# Power_Supply.net
KiCad netlist of a schematic drawn in Altium Designer
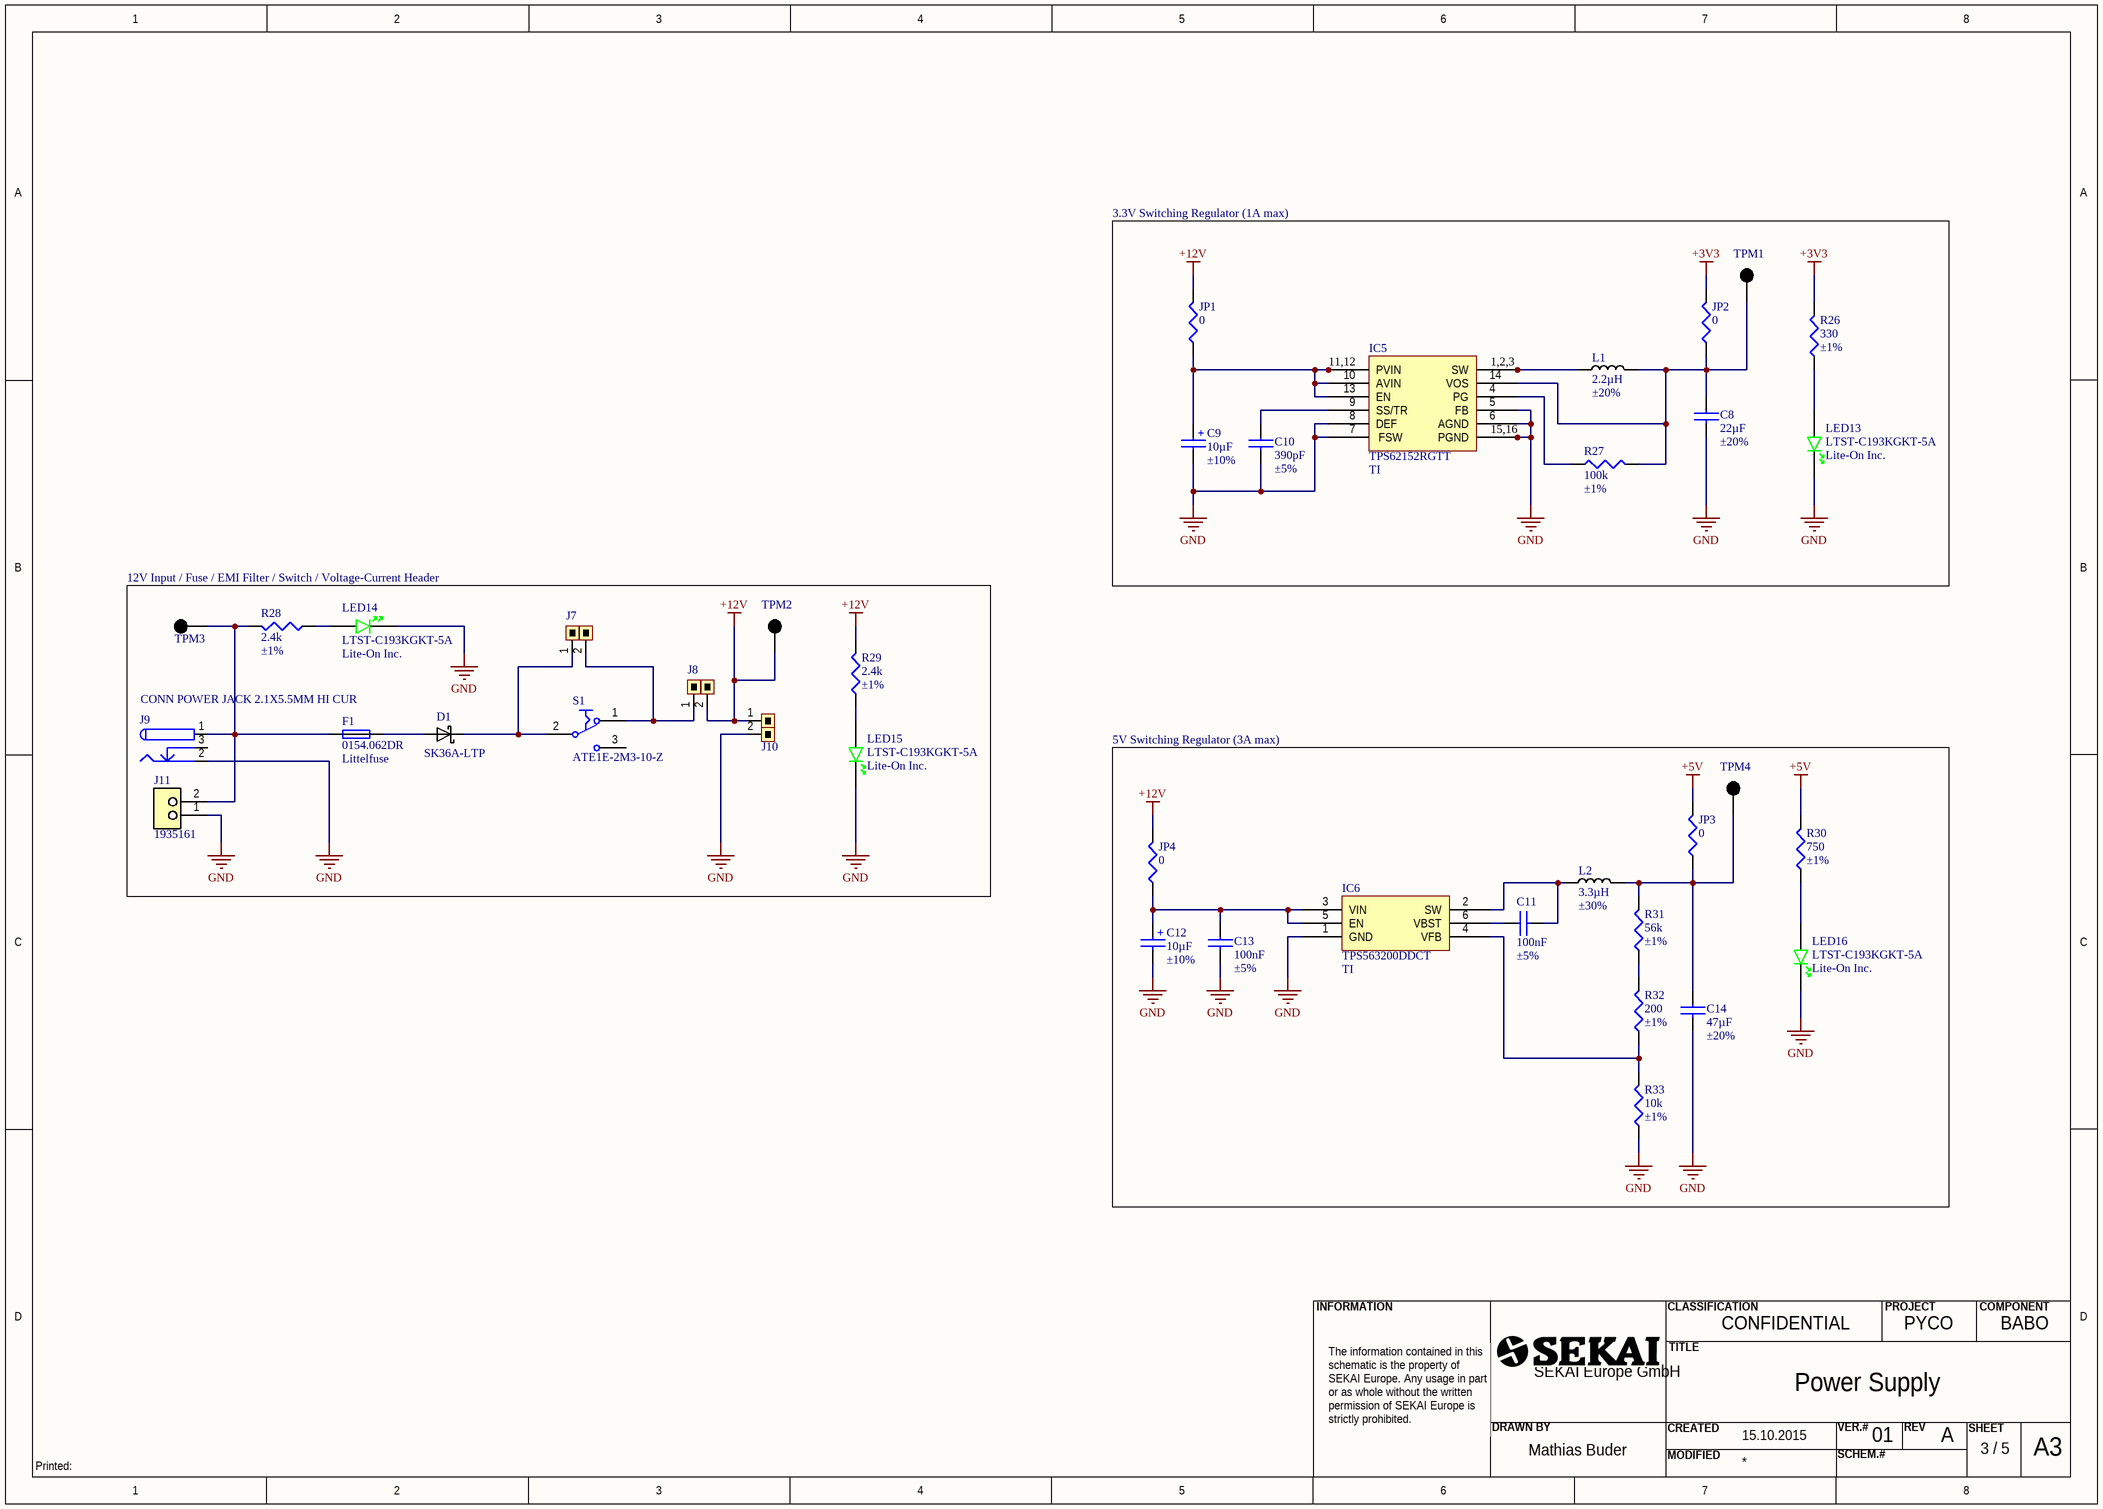
[diagram p0: Power Supply.SchDoc]

(export (version "E")
  (design (tool "Eeschema 10.0.6"))
  (components
    (comp (ref "C8")
      (value "C2012X5R0J226M125AC")
      (footprint "C0805")
      (description "CAP CER 22UF 6.3V X5R 0805")
      (fields
        (field (name "MANUFACTURER") "TDK Corporation")
        (field (name "CAPACITANCE") "22µF")
        (field (name "TOLERANCE") "±20%")
      )
      (libsource (lib "CAP") (part "C2012X5R0J226M125AC"))
    )
    (comp (ref "C9")
      (value "T491A106K016AT")
      (footprint "C1206")
      (description "CAP TANT 10UF 16V 10% 1206")
      (fields
        (field (name "MANUFACTURER") "Kemet")
        (field (name "KAPAZITÄT") "10µF")
        (field (name "TOLERANZ") "±10%")
      )
      (libsource (lib "CAP") (part "T491A106K016AT"))
    )
    (comp (ref "C10")
      (value "GRM1885C1H391JA01D")
      (footprint "C0603")
      (description "CAP CER 390PF 50V NP0 0603")
      (fields
        (field (name "MANUFACTURER") "Murata Electronics North America")
        (field (name "CAPACITANCE") "390pF")
        (field (name "TOLERANCE") "±5%")
      )
      (libsource (lib "CAP") (part "GRM1885C1H391JA01D"))
    )
    (comp (ref "C11")
      (value "C0603C104J4RACTU")
      (footprint "C0603")
      (description "CAP CER 100NF 16V 5% X7R 0603")
      (fields
        (field (name "MANUFACTURER") "Kemet")
        (field (name "KAPAZITÄT") "100nF")
        (field (name "TOLERANZ") "±5%")
      )
      (libsource (lib "CAP") (part "C0603C104J4RACTU"))
    )
    (comp (ref "C12")
      (value "T491A106K016AT")
      (footprint "C1206")
      (description "CAP TANT 10UF 16V 10% 1206")
      (fields
        (field (name "MANUFACTURER") "Kemet")
        (field (name "KAPAZITÄT") "10µF")
        (field (name "TOLERANZ") "±10%")
      )
      (libsource (lib "CAP") (part "T491A106K016AT"))
    )
    (comp (ref "C13")
      (value "C0603C104J4RACTU")
      (footprint "C0603")
      (description "CAP CER 100NF 16V 5% X7R 0603")
      (fields
        (field (name "MANUFACTURER") "Kemet")
        (field (name "KAPAZITÄT") "100nF")
        (field (name "TOLERANZ") "±5%")
      )
      (libsource (lib "CAP") (part "C0603C104J4RACTU"))
    )
    (comp (ref "C14")
      (value "C3216X6S1A476M160AC")
      (footprint "C1206")
      (description "CAP CER 47UF 10V X6S 1206")
      (fields
        (field (name "MANUFACTURER") "TDK Corporation")
        (field (name "CAPACITANCE") "47µF")
        (field (name "TOLERANCE") "±20%")
      )
      (libsource (lib "CAP") (part "C3216X6S1A476M160AC"))
    )
    (comp (ref "D1")
      (value "SK36A-LTP")
      (footprint "DO-214AC")
      (description "DIODE SCHOTTKY 60V 3A DO214AC")
      (fields (field (name "MANUFACTURER") "Micro Commercial Co"))
      (libsource (lib "DIODE_MicroCommercial") (part "SK36A-LTP"))
    )
    (comp (ref "F1")
      (value "0154.062DR")
      (footprint "0154.062DR")
      (description "FUSE BRD MNT 62MA 125VAC/VDC SMD")
      (fields (field (name "MANUFACTURER") "Littelfuse"))
      (libsource (lib "FUSE_LittleFuse") (part "0154.062DR"))
    )
    (comp (ref "IC5")
      (value "TPS62152RGTT")
      (footprint "QFN16")
      (description "IC REG BUCK 3.3V 1A SYNC 16QFN")
      (fields (field (name "MANUFACTURER") "TI"))
      (libsource (lib "BUCK_TI") (part "TPS62152RGTT"))
    )
    (comp (ref "IC6")
      (value "TPS563200DDCT")
      (footprint "SOT23-6")
      (description "IC REG BUCK ADJ 3A SYNC 6SOT")
      (fields (field (name "MANUFACTURER") "TI"))
      (libsource (lib "BUCK_TI") (part "TPS563200DDCT"))
    )
    (comp (ref "J7")
      (value "1x2")
      (footprint "Post Height Terminal Strip 1x2")
      (libsource (lib "") (part "Header 1x2_1"))
    )
    (comp (ref "J8")
      (value "1x2")
      (footprint "Post Height Terminal Strip 1x2")
      (libsource (lib "") (part "Header 1x2_1"))
    )
    (comp (ref "J9")
      (value "CONN POWER JACK 2.1X5.5MM HI CUR")
      (footprint "CP-002AHPJCT-ND")
      (fields
        (field (name "MANUFACTURER") "CUI Inc")
        (field (name "MANUFACTURER PART NUMBER") "PJ-002AH-SMT-TR")
      )
      (libsource (lib "CON_DC") (part "PJ-002AH-SMT-TR"))
    )
    (comp (ref "J10")
      (value "1x2")
      (footprint "Post Height Terminal Strip 1x2")
      (libsource (lib "CON_Standard") (part "Header 1x2"))
    )
    (comp (ref "J11")
      (value "1935161")
      (footprint "2 POS Screw Terminal")
      (description "TERM BLOCK PCB 2POS 5.0MM GREEN")
      (fields (field (name "MANUFACTURER") "Phoenix Contact") (field (name "VOLTAGE") "300V"))
      (libsource (lib "CON_PHOENIX") (part "1935161"))
    )
    (comp (ref "JP1")
      (value "ERJ-3GEY0R00V")
      (footprint "R0603")
      (description "RES SMD 0 OHM JUMPER 1/10W")
      (fields
        (field (name "MANUFACTURER") "Panasonic Electronic Components")
        (field (name "RESISTANCE (OHMS)") "0")
      )
      (libsource (lib "RES") (part "ERJ-3GEY0R00V"))
    )
    (comp (ref "JP2")
      (value "ERJ-3GEY0R00V")
      (footprint "R0603")
      (description "RES SMD 0 OHM JUMPER 1/10W")
      (fields
        (field (name "MANUFACTURER") "Panasonic Electronic Components")
        (field (name "RESISTANCE (OHMS)") "0")
      )
      (libsource (lib "RES") (part "ERJ-3GEY0R00V"))
    )
    (comp (ref "JP3")
      (value "ERJ-3GEY0R00V")
      (footprint "R0603")
      (description "RES SMD 0 OHM JUMPER 1/10W")
      (fields
        (field (name "MANUFACTURER") "Panasonic Electronic Components")
        (field (name "RESISTANCE (OHMS)") "0")
      )
      (libsource (lib "RES") (part "ERJ-3GEY0R00V"))
    )
    (comp (ref "JP4")
      (value "ERJ-3GEY0R00V")
      (footprint "R0603")
      (description "RES SMD 0 OHM JUMPER 1/10W")
      (fields
        (field (name "MANUFACTURER") "Panasonic Electronic Components")
        (field (name "RESISTANCE (OHMS)") "0")
      )
      (libsource (lib "RES") (part "ERJ-3GEY0R00V"))
    )
    (comp (ref "L1")
      (value "SDR0403-2R2ML")
      (footprint "IND-LQH32CN220K53L 2 11")
      (description "FIXED IND 2.2UH 2.6A 47 MOHM SMD")
      (fields
        (field (name "MANUFACTURER") "Bourns Inc.")
        (field (name "INDUCTANCE") "2.2µH")
        (field (name "TOLERANCE") "±20%")
      )
      (libsource (lib "IND") (part "SDR0403-2R2ML"))
    )
    (comp (ref "L2")
      (value "SRR6038-3R3Y")
      (footprint "SRR6038-3R3Y")
      (description "FIXED IND 3.3UH 3.5A 20 MOHM SMD")
      (fields
        (field (name "MANUFACTURER") "Bourns")
        (field (name "INDUCTANCE") "3.3µH")
        (field (name "TOLERANCE") "±30%")
      )
      (libsource (lib "IND") (part "SRR6038-3R3Y"))
    )
    (comp (ref "LED13")
      (value "LTST-C193KGKT-5A")
      (footprint "LED0603-GREEN")
      (description "LED GREEN CLEAR 0603 SMD")
      (fields (field (name "MANUFACTURER") "Lite-On Inc."))
      (libsource (lib "LED_Standard") (part "LTST-C193KGKT-5A"))
    )
    (comp (ref "LED14")
      (value "LTST-C193KGKT-5A")
      (footprint "LED0603-GREEN")
      (description "LED GREEN CLEAR 0603 SMD")
      (fields (field (name "MANUFACTURER") "Lite-On Inc."))
      (libsource (lib "LED_Standard") (part "LTST-C193KGKT-5A"))
    )
    (comp (ref "LED15")
      (value "LTST-C193KGKT-5A")
      (footprint "LED0603-GREEN")
      (description "LED GREEN CLEAR 0603 SMD")
      (fields (field (name "MANUFACTURER") "Lite-On Inc."))
      (libsource (lib "LED_Standard") (part "LTST-C193KGKT-5A"))
    )
    (comp (ref "LED16")
      (value "LTST-C193KGKT-5A")
      (footprint "LED0603-GREEN")
      (description "LED GREEN CLEAR 0603 SMD")
      (fields (field (name "MANUFACTURER") "Lite-On Inc."))
      (libsource (lib "LED_Standard") (part "LTST-C193KGKT-5A"))
    )
    (comp (ref "R26")
      (value "ERJ-3EKF3300V")
      (footprint "R0603")
      (description "RES SMD 330 OHM 1% 1/10W 0603")
      (fields
        (field (name "MANUFACTURER") "Panasonic Electronic Components")
        (field (name "RESISTANCE (OHMS)") "330")
        (field (name "TOLERANCE") "±1%")
      )
      (libsource (lib "RES") (part "ERJ-3EKF3300V"))
    )
    (comp (ref "R27")
      (value "ERJ-3EKF1003V")
      (footprint "R0603")
      (description "RES SMD 100K OHM 1% 1/10W 0603")
      (fields
        (field (name "MANUFACTURER") "Panasonic Electronic Components")
        (field (name "RESISTANCE (OHMS)") "100k")
        (field (name "TOLERANCE") "±1%")
      )
      (libsource (lib "RES") (part "ERJ-3EKF1003V"))
    )
    (comp (ref "R28")
      (value "ERJ-3EKF2401V")
      (footprint "R0603")
      (description "RES SMD 2.4K OHM 1% 1/10W 0603")
      (fields
        (field (name "MANUFACTURER") "Panasonic Electronic Components")
        (field (name "RESISTANCE (OHMS)") "2.4k")
        (field (name "TOLERANCE") "±1%")
      )
      (libsource (lib "RES") (part "ERJ-3EKF2401V"))
    )
    (comp (ref "R29")
      (value "ERJ-3EKF2401V")
      (footprint "R0603")
      (description "RES SMD 2.4K OHM 1% 1/10W 0603")
      (fields
        (field (name "MANUFACTURER") "Panasonic Electronic Components")
        (field (name "RESISTANCE (OHMS)") "2.4k")
        (field (name "TOLERANCE") "±1%")
      )
      (libsource (lib "RES") (part "ERJ-3EKF2401V"))
    )
    (comp (ref "R30")
      (value "ERJ-3EKF7500V")
      (footprint "R0603")
      (description "RES SMD 750 OHM 1% 1/10W 0603")
      (fields
        (field (name "MANUFACTURER") "Panasonic Electronic Components")
        (field (name "RESISTANCE (OHMS)") "750")
        (field (name "TOLERANCE") "±1%")
      )
      (libsource (lib "RES") (part "ERJ-3EKF7500V"))
    )
    (comp (ref "R31")
      (value "ERJ-3EKF5602V")
      (footprint "R0603")
      (description "RES SMD 56K OHM 1% 1/10W 0603")
      (fields
        (field (name "MANUFACTURER") "Panasonic Electronic Components")
        (field (name "RESISTANCE (OHMS)") "56k")
        (field (name "TOLERANCE") "±1%")
      )
      (libsource (lib "RES") (part "ERJ-3EKF5602V"))
    )
    (comp (ref "R32")
      (value "ERJ-3EKF2000V")
      (footprint "R0603")
      (description "RES SMD 200 OHM 1% 1/10W 0603")
      (fields
        (field (name "MANUFACTURER") "Panasonic Electronic Components")
        (field (name "RESISTANCE (OHMS)") "200")
        (field (name "TOLERANCE") "±1%")
      )
      (libsource (lib "RES") (part "ERJ-3EKF2000V"))
    )
    (comp (ref "R33")
      (value "ERJ-3EKF1002V")
      (footprint "R0603")
      (description "RES SMD 10K OHM 1% 1/10W 0603")
      (fields
        (field (name "MANUFACTURER") "Panasonic Electronic Components")
        (field (name "RESISTANCE (OHMS)") "10k")
        (field (name "TOLERANCE") "±1%")
      )
      (libsource (lib "RES") (part "ERJ-3EKF1002V"))
    )
    (comp (ref "S1")
      (value "ATE1E-2M3-10-Z")
      (footprint "ATE1E-2M3-10-Z")
      (description "SWITCH TOGGLE SPDT 50MA 48V")
      (fields (field (name "MANUFACTURER") "Copal Electronics Inc"))
      (libsource (lib "SW_MECH") (part "ATE1E-2M3-10-Z"))
    )
    (comp (ref "TPM1")
      (value "TestPoint-M")
      (footprint "TestPoint-M")
      (libsource (lib "Misc") (part "TestPoint-M"))
    )
    (comp (ref "TPM2")
      (value "TestPoint-M")
      (footprint "TestPoint-M")
      (libsource (lib "Misc") (part "TestPoint-M"))
    )
    (comp (ref "TPM3")
      (value "TestPoint-M")
      (footprint "TestPoint-M")
      (libsource (lib "Misc") (part "TestPoint-M"))
    )
    (comp (ref "TPM4")
      (value "TestPoint-M")
      (footprint "TestPoint-M")
      (libsource (lib "Misc") (part "TestPoint-M"))
    )
  )
  (nets
    (net (code "1") (name "+3V3") (class "Default")
      (node (ref "JP2") (pin "2") (pinfunction "2_2") (pintype "passive"))
      (node (ref "R26") (pin "2") (pinfunction "2_2") (pintype "passive"))
    )
    (net (code "2") (name "+5V") (class "Default")
      (node (ref "JP3") (pin "2") (pinfunction "2_2") (pintype "passive"))
      (node (ref "R30") (pin "2") (pinfunction "2_2") (pintype "passive"))
    )
    (net (code "3") (name "+12V") (class "Default")
      (node (ref "J10") (pin "1") (pinfunction "1_1") (pintype "passive"))
      (node (ref "J8") (pin "2") (pinfunction "2_2") (pintype "passive"))
      (node (ref "JP1") (pin "2") (pinfunction "2_2") (pintype "passive"))
      (node (ref "JP4") (pin "2") (pinfunction "2_2") (pintype "passive"))
      (node (ref "R29") (pin "2") (pinfunction "2_2") (pintype "passive"))
      (node (ref "TPM2") (pin "1") (pinfunction "1_1") (pintype "passive"))
    )
    (net (code "4") (name "GND") (class "Default")
      (node (ref "C10") (pin "2") (pinfunction "2_2") (pintype "passive"))
      (node (ref "C12") (pin "2") (pinfunction "2_2") (pintype "passive"))
      (node (ref "C13") (pin "2") (pinfunction "2_2") (pintype "passive"))
      (node (ref "C14") (pin "2") (pinfunction "2_2") (pintype "passive"))
      (node (ref "C8") (pin "2") (pinfunction "2_2") (pintype "passive"))
      (node (ref "C9") (pin "2") (pinfunction "2_2") (pintype "passive"))
      (node (ref "IC5") (pin "15") (pinfunction "PGND_15") (pintype "passive"))
      (node (ref "IC5") (pin "16") (pinfunction "PGND_16") (pintype "passive"))
      (node (ref "IC5") (pin "5") (pinfunction "FB_5") (pintype "passive"))
      (node (ref "IC5") (pin "6") (pinfunction "AGND_6") (pintype "passive"))
      (node (ref "IC5") (pin "7") (pinfunction "FSW_7") (pintype "passive"))
      (node (ref "IC5") (pin "8") (pinfunction "DEF_8") (pintype "passive"))
      (node (ref "IC6") (pin "1") (pinfunction "GND_1") (pintype "passive"))
      (node (ref "J10") (pin "2") (pinfunction "2_2") (pintype "passive"))
      (node (ref "J11") (pin "1") (pinfunction "1_1") (pintype "passive"))
      (node (ref "J9") (pin "2") (pinfunction "2_2") (pintype "power_in"))
      (node (ref "LED13") (pin "2") (pinfunction "CATHODE_2") (pintype "passive"))
      (node (ref "LED14") (pin "2") (pinfunction "CATHODE_2") (pintype "passive"))
      (node (ref "LED15") (pin "2") (pinfunction "CATHODE_2") (pintype "passive"))
      (node (ref "LED16") (pin "2") (pinfunction "CATHODE_2") (pintype "passive"))
      (node (ref "R33") (pin "1") (pinfunction "1_1") (pintype "passive"))
    )
    (net (code "5") (name "Net-(C14-Pad1)") (class "Default")
      (node (ref "C14") (pin "1") (pinfunction "1_1") (pintype "passive"))
      (node (ref "JP3") (pin "1") (pinfunction "1_1") (pintype "passive"))
      (node (ref "L2") (pin "2") (pinfunction "2_2") (pintype "passive"))
      (node (ref "R31") (pin "2") (pinfunction "2_2") (pintype "passive"))
      (node (ref "TPM4") (pin "1") (pinfunction "1_1") (pintype "passive"))
    )
    (net (code "6") (name "Net-(D1-ANODE)") (class "Default")
      (node (ref "D1") (pin "1") (pinfunction "ANODE_1") (pintype "passive"))
      (node (ref "F1") (pin "2") (pinfunction "2_2") (pintype "passive"))
    )
    (net (code "7") (name "Net-(D1-CATHODE)") (class "Default")
      (node (ref "D1") (pin "2") (pinfunction "CATHODE_2") (pintype "passive"))
      (node (ref "J7") (pin "1") (pinfunction "1_1") (pintype "passive"))
      (node (ref "S1") (pin "2") (pinfunction "2_2") (pintype "passive"))
    )
    (net (code "8") (name "Net-(F1-Pad1)") (class "Default")
      (node (ref "F1") (pin "1") (pinfunction "1_1") (pintype "passive"))
      (node (ref "J11") (pin "2") (pinfunction "2_2") (pintype "passive"))
      (node (ref "J9") (pin "1") (pinfunction "1_1") (pintype "power_in"))
      (node (ref "R28") (pin "2") (pinfunction "2_2") (pintype "passive"))
      (node (ref "TPM3") (pin "1") (pinfunction "1_1") (pintype "passive"))
    )
    (net (code "9") (name "Net-(IC5-AVIN)") (class "Default")
      (node (ref "C9") (pin "1") (pinfunction "1_1") (pintype "passive"))
      (node (ref "IC5") (pin "10") (pinfunction "AVIN_10") (pintype "passive"))
      (node (ref "IC5") (pin "11") (pinfunction "PVIN_11") (pintype "passive"))
      (node (ref "IC5") (pin "12") (pinfunction "PVIN_12") (pintype "passive"))
      (node (ref "IC5") (pin "13") (pinfunction "EN_13") (pintype "passive"))
      (node (ref "JP1") (pin "1") (pinfunction "1_1") (pintype "passive"))
    )
    (net (code "10") (name "Net-(IC5-PG)") (class "Default")
      (node (ref "IC5") (pin "4") (pinfunction "PG_4") (pintype "passive"))
      (node (ref "R27") (pin "1") (pinfunction "1_1") (pintype "passive"))
    )
    (net (code "11") (name "Net-(IC5-SS{slash}TR)") (class "Default")
      (node (ref "C10") (pin "1") (pinfunction "1_1") (pintype "passive"))
      (node (ref "IC5") (pin "9") (pinfunction "SS/TR_9") (pintype "passive"))
    )
    (net (code "12") (name "Net-(IC5-SW-Pad1)") (class "Default")
      (node (ref "IC5") (pin "1") (pinfunction "SW_1") (pintype "passive"))
      (node (ref "IC5") (pin "2") (pinfunction "SW_2") (pintype "passive"))
      (node (ref "IC5") (pin "3") (pinfunction "SW_3") (pintype "passive"))
      (node (ref "L1") (pin "1") (pinfunction "1_1") (pintype "passive"))
    )
    (net (code "13") (name "Net-(IC5-VOS)") (class "Default")
      (node (ref "C8") (pin "1") (pinfunction "1_1") (pintype "passive"))
      (node (ref "IC5") (pin "14") (pinfunction "VOS_14") (pintype "passive"))
      (node (ref "JP2") (pin "1") (pinfunction "1_1") (pintype "passive"))
      (node (ref "L1") (pin "2") (pinfunction "2_2") (pintype "passive"))
      (node (ref "R27") (pin "2") (pinfunction "2_2") (pintype "passive"))
      (node (ref "TPM1") (pin "1") (pinfunction "1_1") (pintype "passive"))
    )
    (net (code "14") (name "Net-(IC6-EN)") (class "Default")
      (node (ref "C12") (pin "1") (pinfunction "1_1") (pintype "passive"))
      (node (ref "C13") (pin "1") (pinfunction "1_1") (pintype "passive"))
      (node (ref "IC6") (pin "3") (pinfunction "VIN_3") (pintype "passive"))
      (node (ref "IC6") (pin "5") (pinfunction "EN_5") (pintype "passive"))
      (node (ref "JP4") (pin "1") (pinfunction "1_1") (pintype "passive"))
    )
    (net (code "15") (name "Net-(IC6-SW)") (class "Default")
      (node (ref "C11") (pin "2") (pinfunction "2_2") (pintype "passive"))
      (node (ref "IC6") (pin "2") (pinfunction "SW_2") (pintype "passive"))
      (node (ref "L2") (pin "1") (pinfunction "1_1") (pintype "passive"))
    )
    (net (code "16") (name "Net-(IC6-VBST)") (class "Default")
      (node (ref "C11") (pin "1") (pinfunction "1_1") (pintype "passive"))
      (node (ref "IC6") (pin "6") (pinfunction "VBST_6") (pintype "passive"))
    )
    (net (code "17") (name "Net-(IC6-VFB)") (class "Default")
      (node (ref "IC6") (pin "4") (pinfunction "VFB_4") (pintype "passive"))
      (node (ref "R32") (pin "1") (pinfunction "1_1") (pintype "passive"))
      (node (ref "R33") (pin "2") (pinfunction "2_2") (pintype "passive"))
    )
    (net (code "18") (name "Net-(J7-Pad2)") (class "Default")
      (node (ref "J7") (pin "2") (pinfunction "2_2") (pintype "passive"))
      (node (ref "J8") (pin "1") (pinfunction "1_1") (pintype "passive"))
      (node (ref "S1") (pin "1") (pinfunction "1_1") (pintype "passive"))
    )
    (net (code "19") (name "Net-(LED13-ANODE)") (class "Default")
      (node (ref "LED13") (pin "1") (pinfunction "ANODE_1") (pintype "passive"))
      (node (ref "R26") (pin "1") (pinfunction "1_1") (pintype "passive"))
    )
    (net (code "20") (name "Net-(LED14-ANODE)") (class "Default")
      (node (ref "LED14") (pin "1") (pinfunction "ANODE_1") (pintype "passive"))
      (node (ref "R28") (pin "1") (pinfunction "1_1") (pintype "passive"))
    )
    (net (code "21") (name "Net-(LED15-ANODE)") (class "Default")
      (node (ref "LED15") (pin "1") (pinfunction "ANODE_1") (pintype "passive"))
      (node (ref "R29") (pin "1") (pinfunction "1_1") (pintype "passive"))
    )
    (net (code "22") (name "Net-(LED16-ANODE)") (class "Default")
      (node (ref "LED16") (pin "1") (pinfunction "ANODE_1") (pintype "passive"))
      (node (ref "R30") (pin "1") (pinfunction "1_1") (pintype "passive"))
    )
    (net (code "23") (name "Net-(R31-Pad1)") (class "Default")
      (node (ref "R31") (pin "1") (pinfunction "1_1") (pintype "passive"))
      (node (ref "R32") (pin "2") (pinfunction "2_2") (pintype "passive"))
    )
    (net (code "24") (name "unconnected-(J9-Pad3)") (class "Default")
      (node (ref "J9") (pin "3") (pinfunction "3_3") (pintype "power_in"))
    )
    (net (code "25") (name "unconnected-(S1-Pad3)") (class "Default")
      (node (ref "S1") (pin "3") (pinfunction "3_3") (pintype "passive"))
    )
  )
)
